# Controller_circuit.net
KiCad netlist of a schematic drawn in Altium Designer
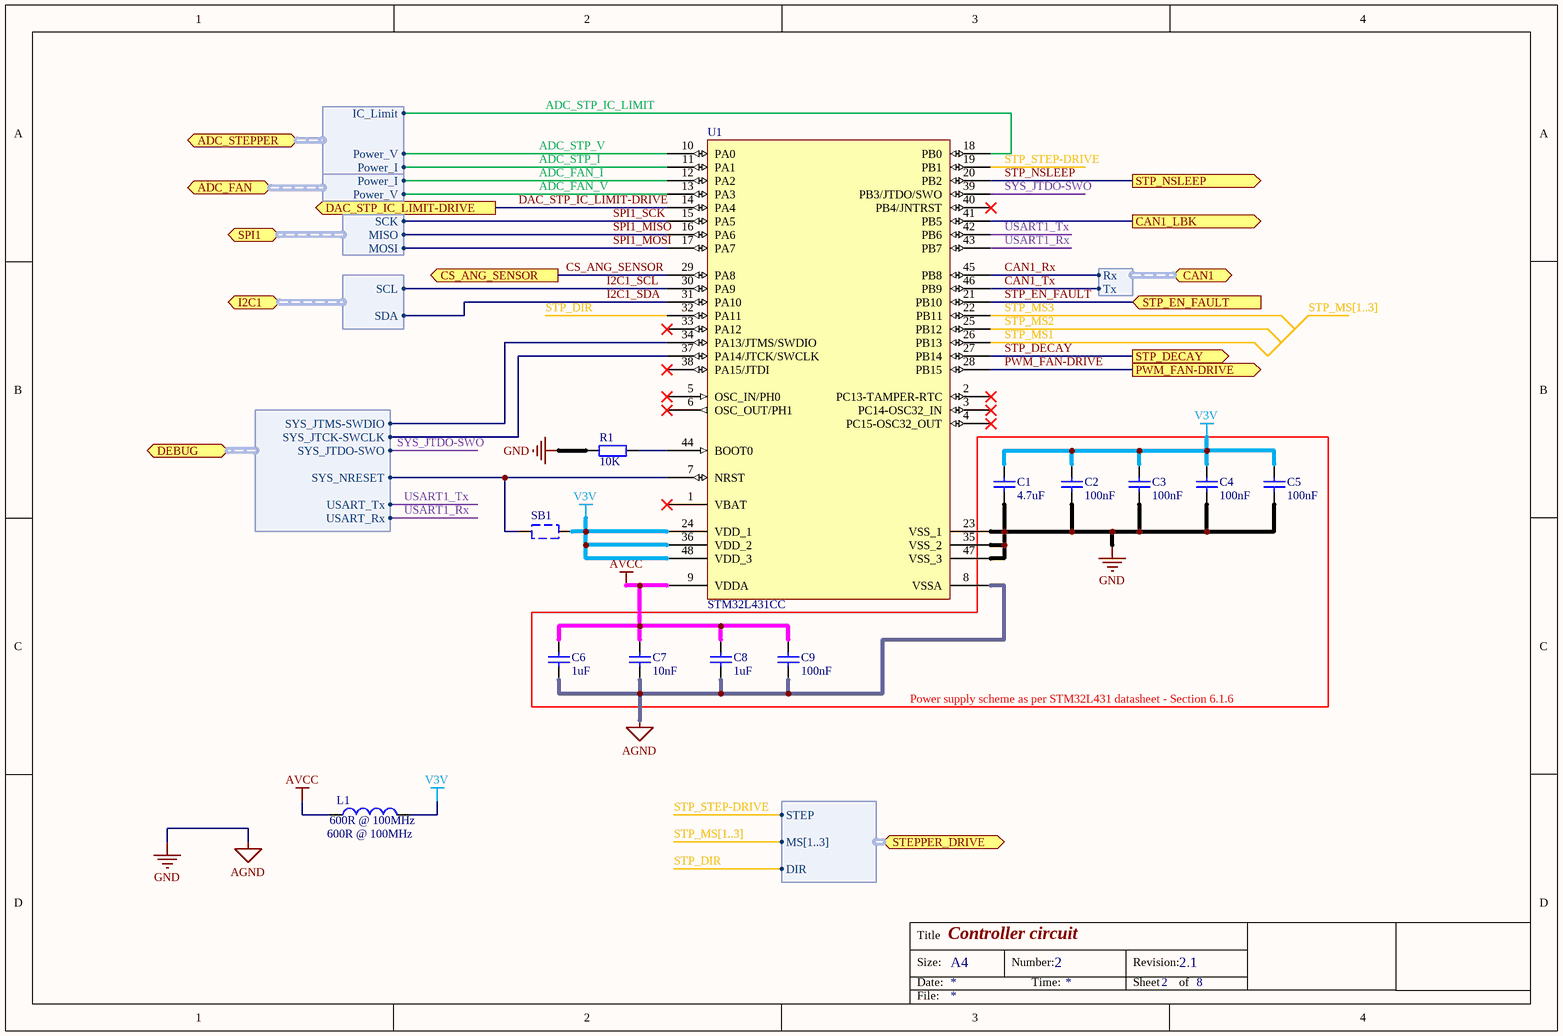
[diagram p0: Controller_circuit.SchDoc]

(export (version "E")
  (design (tool "Eeschema 10.0.6"))
  (components
    (comp (ref "C1")
      (value "4.7uF")
      (footprint "CAPC1608X06N (0603)")
      (description "Capacitor (Semiconductor SIM Model)")
      (fields (field (name "Comment") "Cap Semi") (field (name "PUBLISHER") "Altium Limited"))
      (libsource (lib "miStepper_SchematicLib") (part "Cap Semi"))
    )
    (comp (ref "C2")
      (value "100nF")
      (footprint "CAPC1608X06N (0603)")
      (description "Capacitor (Semiconductor SIM Model)")
      (fields (field (name "Comment") "Cap Semi") (field (name "PUBLISHER") "Altium Limited"))
      (libsource (lib "miStepper_SchematicLib") (part "Cap Semi"))
    )
    (comp (ref "C3")
      (value "100nF")
      (footprint "CAPC1608X06N (0603)")
      (description "Capacitor (Semiconductor SIM Model)")
      (fields (field (name "Comment") "Cap Semi") (field (name "PUBLISHER") "Altium Limited"))
      (libsource (lib "miStepper_SchematicLib") (part "Cap Semi"))
    )
    (comp (ref "C4")
      (value "100nF")
      (footprint "CAPC1608X06N (0603)")
      (description "Capacitor (Semiconductor SIM Model)")
      (fields (field (name "Comment") "Cap Semi") (field (name "PUBLISHER") "Altium Limited"))
      (libsource (lib "miStepper_SchematicLib") (part "Cap Semi"))
    )
    (comp (ref "C5")
      (value "100nF")
      (footprint "CAPC1608X06N (0603)")
      (description "Capacitor (Semiconductor SIM Model)")
      (fields (field (name "Comment") "Cap Semi") (field (name "PUBLISHER") "Altium Limited"))
      (libsource (lib "miStepper_SchematicLib") (part "Cap Semi"))
    )
    (comp (ref "C6")
      (value "1uF")
      (footprint "CAPC1608X06N (0603)")
      (description "Capacitor (Semiconductor SIM Model)")
      (fields (field (name "Comment") "Cap Semi") (field (name "PUBLISHER") "Altium Limited"))
      (libsource (lib "miStepper_SchematicLib") (part "Cap Semi"))
    )
    (comp (ref "C7")
      (value "10nF")
      (footprint "CAPC1608X06N (0603)")
      (description "Capacitor (Semiconductor SIM Model)")
      (fields (field (name "Comment") "Cap Semi") (field (name "PUBLISHER") "Altium Limited"))
      (libsource (lib "miStepper_SchematicLib") (part "Cap Semi"))
    )
    (comp (ref "C8")
      (value "1uF")
      (footprint "CAPC1608X06N (0603)")
      (description "Capacitor (Semiconductor SIM Model)")
      (fields (field (name "Comment") "Cap Semi") (field (name "PUBLISHER") "Altium Limited"))
      (libsource (lib "miStepper_SchematicLib") (part "Cap Semi"))
    )
    (comp (ref "C9")
      (value "100nF")
      (footprint "CAPC1608X06N (0603)")
      (description "Capacitor (Semiconductor SIM Model)")
      (fields (field (name "Comment") "Cap Semi") (field (name "PUBLISHER") "Altium Limited"))
      (libsource (lib "miStepper_SchematicLib") (part "Cap Semi"))
    )
    (comp (ref "L1")
      (value "600R @ 100MHz")
      (footprint "INDC1608X06N")
      (description "Inductor with ferrite bead")
      (fields (field (name "ALTIUM_VALUE") "600R @ 100MHz"))
      (libsource (lib "miStepper_SchematicLib") (part "Ferrite Bead"))
    )
    (comp (ref "R1")
      (value "10K")
      (footprint "RESC1608X06N (0603)")
      (description "Resistor")
      (fields (field (name "Comment") "Res") (field (name "PUBLISHER") "Altium Limited"))
      (libsource (lib "miStepper_SchematicLib") (part "Res"))
    )
    (comp (ref "SB1")
      (value "Option_Res")
      (footprint "RESC1608X06N (0603)")
      (description "Resistor")
      (fields (field (name "PUBLISHER") "Altium Limited"))
      (libsource (lib "miStepper_SchematicLib") (part "Option_Resistor"))
    )
    (comp (ref "U1")
      (value "STM32L431CC")
      (footprint "LQFP48_L")
      (description "STM32 ARM-based 32-bit MCU with 32 Kbytes Flash, 48-pin LQFP, Industrial Temperature")
      (fields (field (name "PUBLISHER") "Altium Limited"))
      (libsource (lib "miStepper_SchematicLib") (part "STM32L431CC"))
    )
  )
  (nets
    (net (code "8") (name "/ADC_FAN_I") (class "Default")
      (node (ref "U1") (pin "12") (pinfunction "PA2_12") (pintype "bidirectional"))
    )
    (net (code "9") (name "/ADC_FAN_V") (class "Default")
      (node (ref "U1") (pin "13") (pinfunction "PA3_13") (pintype "bidirectional"))
    )
    (net (code "10") (name "/ADC_STP_I") (class "Default")
      (node (ref "U1") (pin "11") (pinfunction "PA1_11") (pintype "bidirectional"))
    )
    (net (code "11") (name "/ADC_STP_IC_LIMIT") (class "Default")
      (node (ref "U1") (pin "18") (pinfunction "PB0_18") (pintype "bidirectional"))
    )
    (net (code "12") (name "/ADC_STP_V") (class "Default")
      (node (ref "U1") (pin "10") (pinfunction "PA0_10") (pintype "bidirectional"))
    )
    (net (code "13") (name "/CAN1_LBK") (class "Default")
      (node (ref "U1") (pin "41") (pinfunction "PB5_41") (pintype "bidirectional"))
    )
    (net (code "14") (name "/CAN1_Rx") (class "Default")
      (node (ref "U1") (pin "45") (pinfunction "PB8_45") (pintype "bidirectional"))
    )
    (net (code "15") (name "/CAN1_Tx") (class "Default")
      (node (ref "U1") (pin "46") (pinfunction "PB9_46") (pintype "bidirectional"))
    )
    (net (code "16") (name "/CS_ANG_SENSOR") (class "Default")
      (node (ref "U1") (pin "29") (pinfunction "PA8_29") (pintype "bidirectional"))
    )
    (net (code "17") (name "/DAC_STP_IC_LIMIT-DRIVE") (class "Default")
      (node (ref "U1") (pin "14") (pinfunction "PA4_14") (pintype "bidirectional"))
    )
    (net (code "18") (name "/I2C1_SCL") (class "Default")
      (node (ref "U1") (pin "30") (pinfunction "PA9_30") (pintype "bidirectional"))
    )
    (net (code "19") (name "/I2C1_SDA") (class "Default")
      (node (ref "U1") (pin "31") (pinfunction "PA10_31") (pintype "bidirectional"))
    )
    (net (code "20") (name "/PWM_FAN-DRIVE") (class "Default")
      (node (ref "U1") (pin "28") (pinfunction "PB15_28") (pintype "bidirectional"))
    )
    (net (code "21") (name "/SPI1_MISO") (class "Default")
      (node (ref "U1") (pin "16") (pinfunction "PA6_16") (pintype "bidirectional"))
    )
    (net (code "22") (name "/SPI1_MOSI") (class "Default")
      (node (ref "U1") (pin "17") (pinfunction "PA7_17") (pintype "bidirectional"))
    )
    (net (code "23") (name "/SPI1_SCK") (class "Default")
      (node (ref "U1") (pin "15") (pinfunction "PA5_15") (pintype "bidirectional"))
    )
    (net (code "24") (name "/STP_DECAY") (class "Default")
      (node (ref "U1") (pin "27") (pinfunction "PB14_27") (pintype "bidirectional"))
    )
    (net (code "25") (name "/STP_DIR") (class "Default")
      (node (ref "U1") (pin "32") (pinfunction "PA11_32") (pintype "bidirectional"))
    )
    (net (code "26") (name "/STP_EN_FAULT") (class "Default")
      (node (ref "U1") (pin "21") (pinfunction "PB10_21") (pintype "bidirectional"))
    )
    (net (code "27") (name "/STP_MS1") (class "Default")
      (node (ref "U1") (pin "26") (pinfunction "PB13_26") (pintype "bidirectional"))
    )
    (net (code "28") (name "/STP_MS2") (class "Default")
      (node (ref "U1") (pin "25") (pinfunction "PB12_25") (pintype "bidirectional"))
    )
    (net (code "29") (name "/STP_MS3") (class "Default")
      (node (ref "U1") (pin "22") (pinfunction "PB11_22") (pintype "bidirectional"))
    )
    (net (code "31") (name "/STP_NSLEEP") (class "Default")
      (node (ref "U1") (pin "20") (pinfunction "PB2_20") (pintype "bidirectional"))
    )
    (net (code "32") (name "/STP_STEP-DRIVE") (class "Default")
      (node (ref "U1") (pin "19") (pinfunction "PB1_19") (pintype "bidirectional"))
    )
    (net (code "33") (name "/SYS_JTCK-SWCLK") (class "Default")
      (node (ref "U1") (pin "37") (pinfunction "PA14/JTCK/SWCLK_37") (pintype "bidirectional"))
    )
    (net (code "34") (name "/SYS_JTDO-SWO") (class "Default")
      (node (ref "U1") (pin "39") (pinfunction "PB3/JTDO/SWO_39") (pintype "bidirectional"))
    )
    (net (code "35") (name "/SYS_JTMS-SWDIO") (class "Default")
      (node (ref "U1") (pin "34") (pinfunction "PA13/JTMS/SWDIO_34") (pintype "bidirectional"))
    )
    (net (code "36") (name "/SYS_NRESET") (class "Default")
      (node (ref "SB1") (pin "1") (pinfunction "1_1") (pintype "passive"))
      (node (ref "U1") (pin "7") (pinfunction "NRST_7") (pintype "bidirectional"))
    )
    (net (code "37") (name "/USART1_Rx") (class "Default")
      (node (ref "U1") (pin "43") (pinfunction "PB7_43") (pintype "bidirectional"))
    )
    (net (code "38") (name "/USART1_Tx") (class "Default")
      (node (ref "U1") (pin "42") (pinfunction "PB6_42") (pintype "bidirectional"))
    )
    (net (code "46") (name "AGND") (class "Default")
      (node (ref "C1") (pin "1") (pinfunction "1_1") (pintype "passive"))
      (node (ref "C2") (pin "1") (pinfunction "1_1") (pintype "passive"))
      (node (ref "C3") (pin "1") (pinfunction "1_1") (pintype "passive"))
      (node (ref "C4") (pin "1") (pinfunction "1_1") (pintype "passive"))
      (node (ref "C5") (pin "1") (pinfunction "1_1") (pintype "passive"))
      (node (ref "C6") (pin "1") (pinfunction "1_1") (pintype "passive"))
      (node (ref "C7") (pin "1") (pinfunction "1_1") (pintype "passive"))
      (node (ref "C8") (pin "1") (pinfunction "1_1") (pintype "passive"))
      (node (ref "C9") (pin "1") (pinfunction "1_1") (pintype "passive"))
      (node (ref "R1") (pin "1") (pinfunction "1_1") (pintype "passive"))
      (node (ref "U1") (pin "23") (pinfunction "VSS_1_23") (pintype "power_in"))
      (node (ref "U1") (pin "35") (pinfunction "VSS_2_35") (pintype "power_in"))
      (node (ref "U1") (pin "47") (pinfunction "VSS_3_47") (pintype "power_in"))
      (node (ref "U1") (pin "8") (pinfunction "VSSA_8") (pintype "power_in"))
    )
    (net (code "47") (name "AVCC") (class "Default")
      (node (ref "C6") (pin "2") (pinfunction "2_2") (pintype "passive"))
      (node (ref "C7") (pin "2") (pinfunction "2_2") (pintype "passive"))
      (node (ref "C8") (pin "2") (pinfunction "2_2") (pintype "passive"))
      (node (ref "C9") (pin "2") (pinfunction "2_2") (pintype "passive"))
      (node (ref "L1") (pin "1") (pinfunction "1_1") (pintype "passive"))
      (node (ref "U1") (pin "9") (pinfunction "VDDA_9") (pintype "power_in"))
    )
    (net (code "48") (name "Net-(U1-BOOT0)") (class "Default")
      (node (ref "R1") (pin "2") (pinfunction "2_2") (pintype "passive"))
      (node (ref "U1") (pin "44") (pinfunction "BOOT0_44") (pintype "input"))
    )
    (net (code "49") (name "V3V") (class "Default")
      (node (ref "C1") (pin "2") (pinfunction "2_2") (pintype "passive"))
      (node (ref "C2") (pin "2") (pinfunction "2_2") (pintype "passive"))
      (node (ref "C3") (pin "2") (pinfunction "2_2") (pintype "passive"))
      (node (ref "C4") (pin "2") (pinfunction "2_2") (pintype "passive"))
      (node (ref "C5") (pin "2") (pinfunction "2_2") (pintype "passive"))
      (node (ref "L1") (pin "2") (pinfunction "2_2") (pintype "passive"))
      (node (ref "SB1") (pin "2") (pinfunction "2_2") (pintype "passive"))
      (node (ref "U1") (pin "24") (pinfunction "VDD_1_24") (pintype "power_in"))
      (node (ref "U1") (pin "36") (pinfunction "VDD_2_36") (pintype "power_in"))
      (node (ref "U1") (pin "48") (pinfunction "VDD_3_48") (pintype "power_in"))
    )
    (net (code "50") (name "unconnected-(U1-OSC_IN{slash}PH0-Pad5)") (class "Default")
      (node (ref "U1") (pin "5") (pinfunction "OSC_IN/PH0_5") (pintype "input+no_connect"))
    )
    (net (code "51") (name "unconnected-(U1-OSC_OUT{slash}PH1-Pad6)") (class "Default")
      (node (ref "U1") (pin "6") (pinfunction "OSC_OUT/PH1_6") (pintype "output+no_connect"))
    )
    (net (code "52") (name "unconnected-(U1-PA12-Pad33)") (class "Default")
      (node (ref "U1") (pin "33") (pinfunction "PA12_33") (pintype "bidirectional+no_connect"))
    )
    (net (code "53") (name "unconnected-(U1-PA15{slash}JTDI-Pad38)") (class "Default")
      (node (ref "U1") (pin "38") (pinfunction "PA15/JTDI_38") (pintype "bidirectional+no_connect"))
    )
    (net (code "54") (name "unconnected-(U1-PB4{slash}JNTRST-Pad40)") (class "Default")
      (node (ref "U1") (pin "40") (pinfunction "PB4/JNTRST_40") (pintype "bidirectional+no_connect"))
    )
    (net (code "55") (name "unconnected-(U1-PC13-TAMPER-RTC-Pad2)") (class "Default")
      (node (ref "U1") (pin "2") (pinfunction "PC13-TAMPER-RTC_2") (pintype "bidirectional+no_connect"))
    )
    (net (code "56") (name "unconnected-(U1-PC14-OSC32_IN-Pad3)") (class "Default")
      (node (ref "U1") (pin "3") (pinfunction "PC14-OSC32_IN_3") (pintype "bidirectional+no_connect"))
    )
    (net (code "57") (name "unconnected-(U1-PC15-OSC32_OUT-Pad4)") (class "Default")
      (node (ref "U1") (pin "4") (pinfunction "PC15-OSC32_OUT_4") (pintype "bidirectional+no_connect"))
    )
    (net (code "58") (name "unconnected-(U1-VBAT-Pad1)") (class "Default")
      (node (ref "U1") (pin "1") (pinfunction "VBAT_1") (pintype "power_in+no_connect"))
    )
  )
)
